# rxdown_blank.net
KiCad netlist of a schematic drawn in Altium Designer
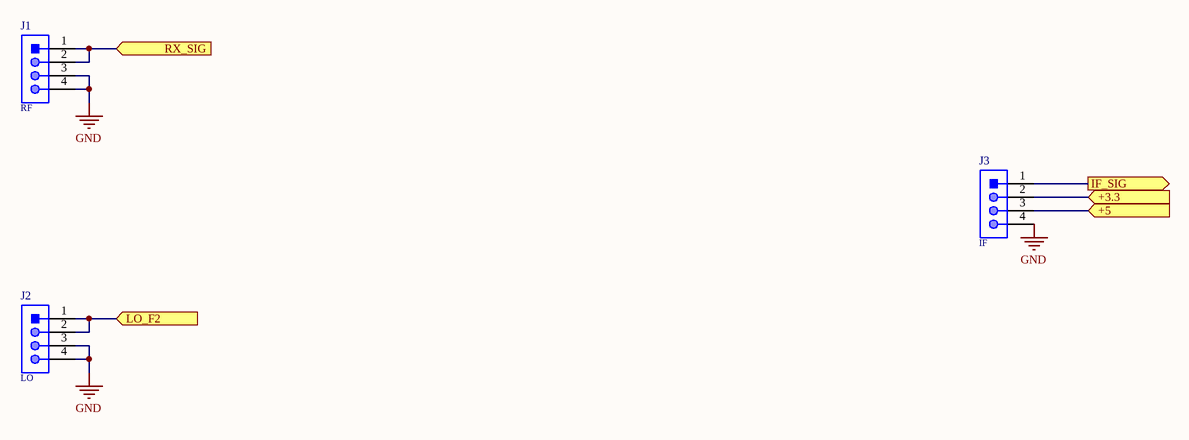
[diagram p0: rxdown_blank.SchDoc]

(export (version "E")
  (design (tool "Eeschema 10.0.6"))
  (components
    (comp (ref "J1")
      (value "RF")
      (footprint "61300411121")
      (description "THT Vertical Pin Header WR-PHD, Pitch 2.54 mm, Single Row, 4 pins")
      (fields
        (field (name "MANUFACTURER") "Wurth Elektronik")
        (field (name "PART NUMBER") "61300411121")
        (field (name "PUBLISHER") "WurthElektronik")
      )
      (libsource (lib "Altium Content Vault") (part "WE-CN-1P-M-R4"))
    )
    (comp (ref "J2")
      (value "LO")
      (footprint "61300411121")
      (description "THT Vertical Pin Header WR-PHD, Pitch 2.54 mm, Single Row, 4 pins")
      (fields
        (field (name "MANUFACTURER") "Wurth Elektronik")
        (field (name "PART NUMBER") "61300411121")
        (field (name "PUBLISHER") "WurthElektronik")
      )
      (libsource (lib "Altium Content Vault") (part "WE-CN-1P-M-R4"))
    )
    (comp (ref "J3")
      (value "IF")
      (footprint "61300411121")
      (description "THT Vertical Pin Header WR-PHD, Pitch 2.54 mm, Single Row, 4 pins")
      (fields
        (field (name "MANUFACTURER") "Wurth Elektronik")
        (field (name "PART NUMBER") "61300411121")
        (field (name "PUBLISHER") "WurthElektronik")
      )
      (libsource (lib "Altium Content Vault") (part "WE-CN-1P-M-R4"))
    )
  )
  (nets
    (net (code "1") (name "/+3.3") (class "Default")
      (node (ref "J3") (pin "2") (pinfunction "2_2") (pintype "passive"))
    )
    (net (code "2") (name "/+5") (class "Default")
      (node (ref "J3") (pin "3") (pinfunction "3_3") (pintype "passive"))
    )
    (net (code "3") (name "/IF_SIG") (class "Default")
      (node (ref "J3") (pin "1") (pinfunction "1_1") (pintype "passive"))
    )
    (net (code "4") (name "/LO_F2") (class "Default")
      (node (ref "J2") (pin "1") (pinfunction "1_1") (pintype "passive"))
      (node (ref "J2") (pin "2") (pinfunction "2_2") (pintype "passive"))
    )
    (net (code "5") (name "/RX_SIG") (class "Default")
      (node (ref "J1") (pin "1") (pinfunction "1_1") (pintype "passive"))
      (node (ref "J1") (pin "2") (pinfunction "2_2") (pintype "passive"))
    )
    (net (code "6") (name "GND") (class "Default")
      (node (ref "J1") (pin "3") (pinfunction "3_3") (pintype "passive"))
      (node (ref "J1") (pin "4") (pinfunction "4_4") (pintype "passive"))
      (node (ref "J2") (pin "3") (pinfunction "3_3") (pintype "passive"))
      (node (ref "J2") (pin "4") (pinfunction "4_4") (pintype "passive"))
      (node (ref "J3") (pin "4") (pinfunction "4_4") (pintype "passive"))
    )
  )
)
